# Crumar_D9U_Main.net
KiCad netlist of a schematic drawn in EAGLE
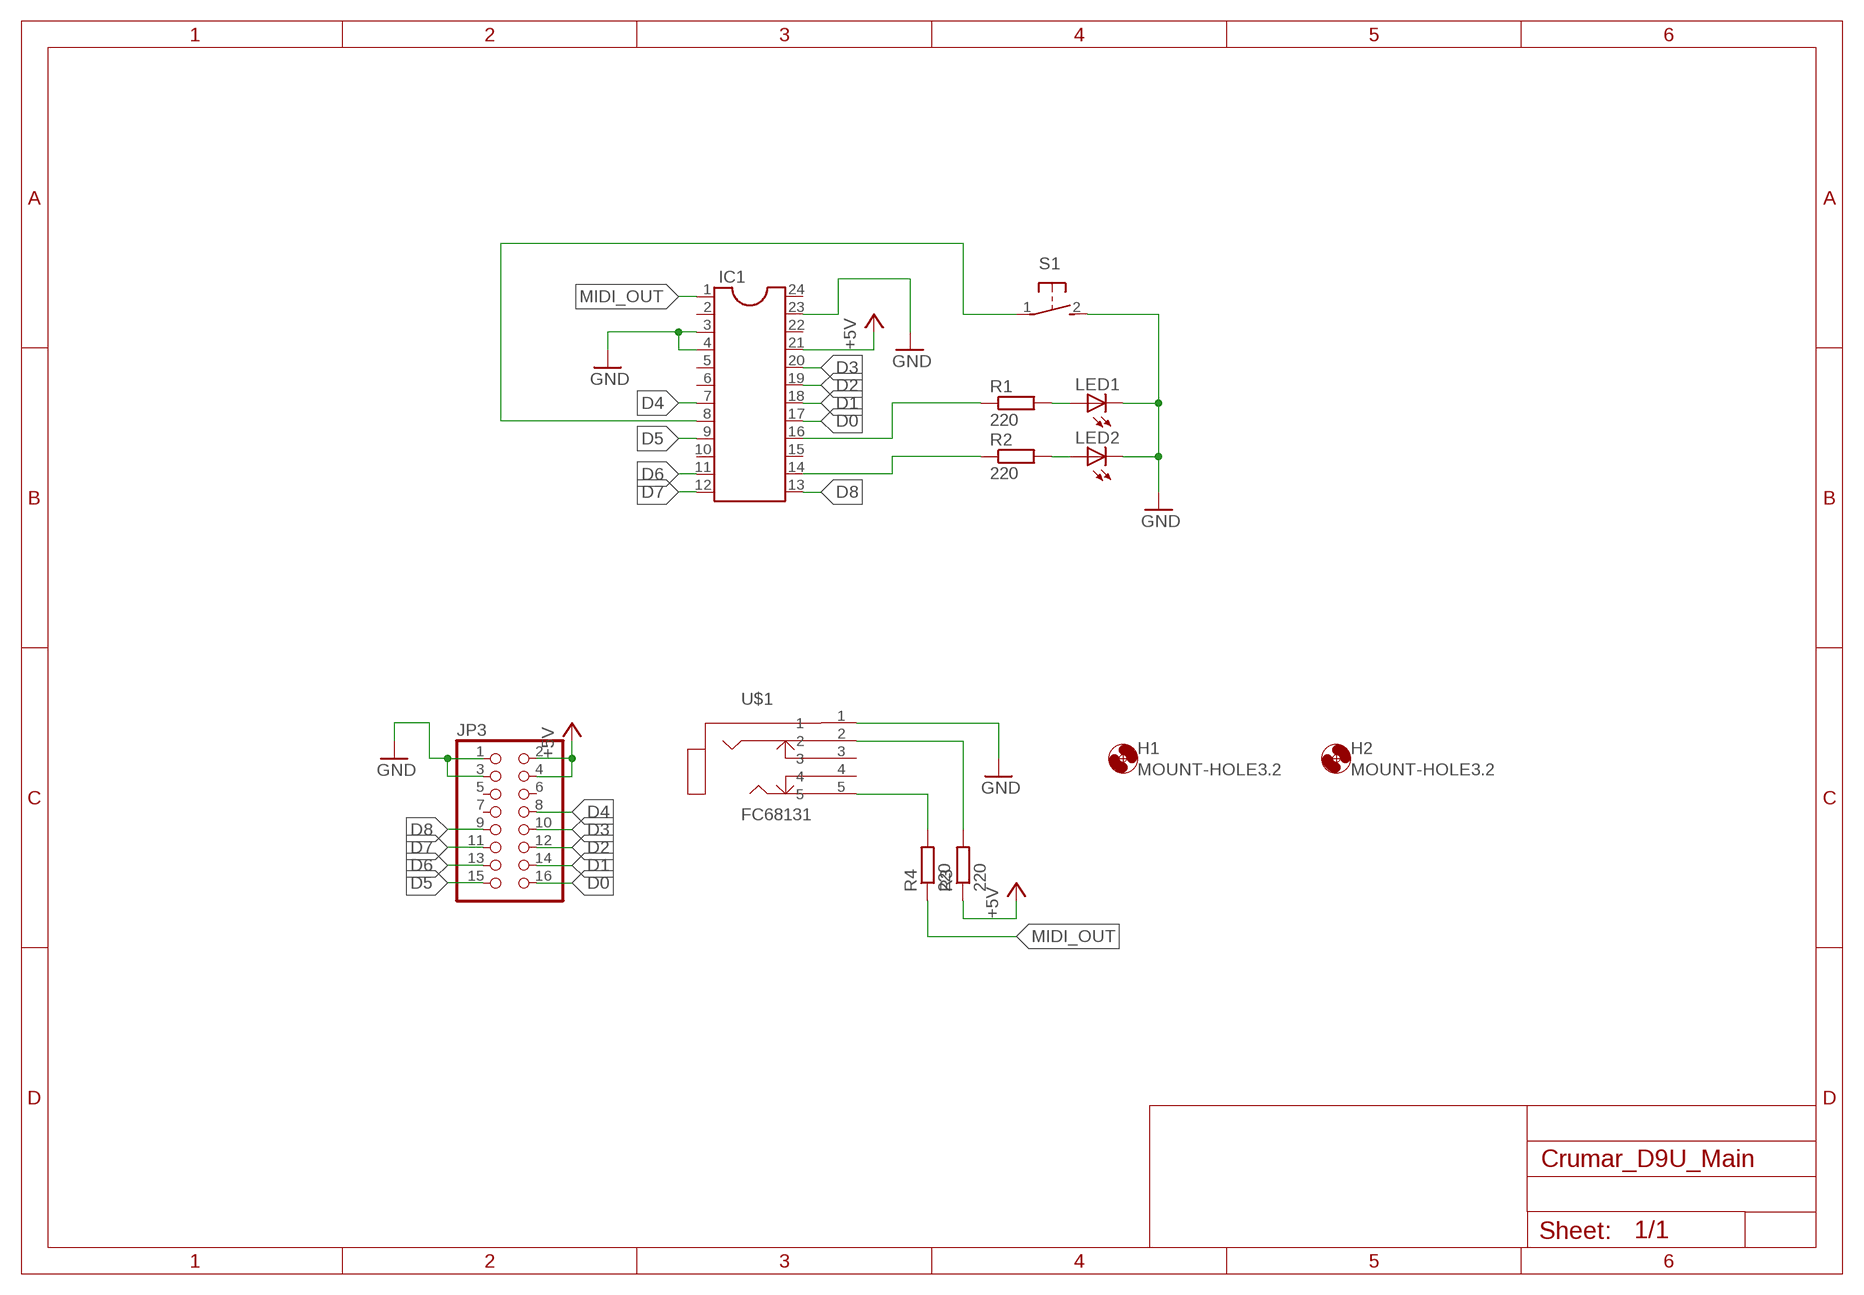
[diagram p0: schematic, sheet 1]

(export (version "E")
  (design (tool "Eeschema 10.0.6"))
  (components
    (comp (ref "H1")
      (value "MOUNT-HOLE3.2")
      (footprint "eagle-import:3,2")
      (libsource (lib "eagle-import") (part "MOUNT-HOLE3.2"))
    )
    (comp (ref "H2")
      (value "MOUNT-HOLE3.2")
      (footprint "eagle-import:3,2")
      (libsource (lib "eagle-import") (part "MOUNT-HOLE3.2"))
    )
    (comp (ref "IC1")
      (value "DIL24-6")
      (footprint "eagle-import:DIL24-6")
      (libsource (lib "eagle-import") (part "DIL24-6"))
    )
    (comp (ref "JP3")
      (value "PINHD-2X8")
      (footprint "eagle-import:2X08")
      (libsource (lib "eagle-import") (part "PINHD-2X8"))
    )
    (comp (ref "LED1")
      (value "LED3MM")
      (footprint "eagle-import:LED3MM")
      (libsource (lib "eagle-import") (part "LED3MM"))
    )
    (comp (ref "LED2")
      (value "LED3MM")
      (footprint "eagle-import:LED3MM")
      (libsource (lib "eagle-import") (part "LED3MM"))
    )
    (comp (ref "R1")
      (value "220")
      (footprint "eagle-import:0207_7")
      (libsource (lib "eagle-import") (part "R-EU_0207/7"))
    )
    (comp (ref "R2")
      (value "220")
      (footprint "eagle-import:0207_7")
      (libsource (lib "eagle-import") (part "R-EU_0207/7"))
    )
    (comp (ref "R3")
      (value "220")
      (footprint "eagle-import:0207_7")
      (libsource (lib "eagle-import") (part "R-EU_0207/7"))
    )
    (comp (ref "R4")
      (value "220")
      (footprint "eagle-import:0207_7")
      (libsource (lib "eagle-import") (part "R-EU_0207/7"))
    )
    (comp (ref "S1")
      (value "31-XX")
      (footprint "eagle-import:B3F-31XX")
      (fields (field (name "MPN") "B3F-3100"))
      (libsource (lib "eagle-import") (part "31-XX"))
    )
    (comp (ref "U$1")
      (value "FC68131")
      (footprint "eagle-import:FC68131-5P")
      (libsource (lib "eagle-import") (part "FC68131"))
    )
  )
  (nets
    (net (code "1") (name "+5V") (class "Default")
      (node (ref "IC1") (pin "21") (pinfunction "21_21") (pintype "passive"))
      (node (ref "JP3") (pin "2") (pinfunction "2_2") (pintype "passive"))
      (node (ref "JP3") (pin "4") (pinfunction "4_4") (pintype "passive"))
      (node (ref "R3") (pin "1") (pinfunction "1_1") (pintype "passive"))
    )
    (net (code "2") (name "D0") (class "Default")
      (node (ref "IC1") (pin "17") (pinfunction "17_17") (pintype "passive"))
      (node (ref "JP3") (pin "16") (pinfunction "16_16") (pintype "passive"))
    )
    (net (code "3") (name "D1") (class "Default")
      (node (ref "IC1") (pin "18") (pinfunction "18_18") (pintype "passive"))
      (node (ref "JP3") (pin "14") (pinfunction "14_14") (pintype "passive"))
    )
    (net (code "4") (name "D2") (class "Default")
      (node (ref "IC1") (pin "19") (pinfunction "19_19") (pintype "passive"))
      (node (ref "JP3") (pin "12") (pinfunction "12_12") (pintype "passive"))
    )
    (net (code "5") (name "D3") (class "Default")
      (node (ref "IC1") (pin "20") (pinfunction "20_20") (pintype "passive"))
      (node (ref "JP3") (pin "10") (pinfunction "10_10") (pintype "passive"))
    )
    (net (code "6") (name "D4") (class "Default")
      (node (ref "IC1") (pin "7") (pinfunction "7_7") (pintype "passive"))
      (node (ref "JP3") (pin "8") (pinfunction "8_8") (pintype "passive"))
    )
    (net (code "7") (name "D5") (class "Default")
      (node (ref "IC1") (pin "9") (pinfunction "9_9") (pintype "passive"))
      (node (ref "JP3") (pin "15") (pinfunction "15_15") (pintype "passive"))
    )
    (net (code "8") (name "D6") (class "Default")
      (node (ref "IC1") (pin "11") (pinfunction "11_11") (pintype "passive"))
      (node (ref "JP3") (pin "13") (pinfunction "13_13") (pintype "passive"))
    )
    (net (code "9") (name "D7") (class "Default")
      (node (ref "IC1") (pin "12") (pinfunction "12_12") (pintype "passive"))
      (node (ref "JP3") (pin "11") (pinfunction "11_11") (pintype "passive"))
    )
    (net (code "10") (name "D8") (class "Default")
      (node (ref "IC1") (pin "13") (pinfunction "13_13") (pintype "passive"))
      (node (ref "JP3") (pin "9") (pinfunction "9_9") (pintype "passive"))
    )
    (net (code "11") (name "GND") (class "Default")
      (node (ref "IC1") (pin "23") (pinfunction "23_23") (pintype "passive"))
      (node (ref "IC1") (pin "3") (pinfunction "3_3") (pintype "passive"))
      (node (ref "IC1") (pin "4") (pinfunction "4_4") (pintype "passive"))
      (node (ref "JP3") (pin "1") (pinfunction "1_1") (pintype "passive"))
      (node (ref "JP3") (pin "3") (pinfunction "3_3") (pintype "passive"))
      (node (ref "LED1") (pin "K") (pinfunction "C_K") (pintype "passive"))
      (node (ref "LED2") (pin "K") (pinfunction "C_K") (pintype "passive"))
      (node (ref "S1") (pin "2") (pinfunction "S_2") (pintype "passive"))
      (node (ref "U$1") (pin "1") (pinfunction "1_1") (pintype "bidirectional"))
    )
    (net (code "12") (name "MIDI_OUT") (class "Default")
      (node (ref "IC1") (pin "1") (pinfunction "1_1") (pintype "passive"))
      (node (ref "R4") (pin "1") (pinfunction "1_1") (pintype "passive"))
    )
    (net (code "13") (name "Net-(IC1-Pad14)") (class "Default")
      (node (ref "IC1") (pin "14") (pinfunction "14_14") (pintype "passive"))
      (node (ref "R2") (pin "1") (pinfunction "1_1") (pintype "passive"))
    )
    (net (code "14") (name "Net-(IC1-Pad16)") (class "Default")
      (node (ref "IC1") (pin "16") (pinfunction "16_16") (pintype "passive"))
      (node (ref "R1") (pin "1") (pinfunction "1_1") (pintype "passive"))
    )
    (net (code "15") (name "Net-(LED1-PadA)") (class "Default")
      (node (ref "LED1") (pin "A") (pinfunction "A_A") (pintype "passive"))
      (node (ref "R1") (pin "2") (pinfunction "2_2") (pintype "passive"))
    )
    (net (code "16") (name "Net-(LED2-PadA)") (class "Default")
      (node (ref "LED2") (pin "A") (pinfunction "A_A") (pintype "passive"))
      (node (ref "R2") (pin "2") (pinfunction "2_2") (pintype "passive"))
    )
    (net (code "17") (name "Net-(R3-Pad2)") (class "Default")
      (node (ref "R3") (pin "2") (pinfunction "2_2") (pintype "passive"))
      (node (ref "U$1") (pin "2") (pinfunction "2_2") (pintype "bidirectional"))
    )
    (net (code "18") (name "Net-(R4-Pad2)") (class "Default")
      (node (ref "R4") (pin "2") (pinfunction "2_2") (pintype "passive"))
      (node (ref "U$1") (pin "5") (pinfunction "5_5") (pintype "bidirectional"))
    )
    (net (code "19") (name "Net-(S1-P)") (class "Default")
      (node (ref "IC1") (pin "8") (pinfunction "8_8") (pintype "passive"))
      (node (ref "S1") (pin "1") (pinfunction "P_1") (pintype "passive"))
    )
    (net (code "20") (name "unconnected-(IC1-Pad2)") (class "Default")
      (node (ref "IC1") (pin "2") (pinfunction "2_2") (pintype "passive"))
    )
    (net (code "21") (name "unconnected-(IC1-Pad5)") (class "Default")
      (node (ref "IC1") (pin "5") (pinfunction "5_5") (pintype "passive"))
    )
    (net (code "22") (name "unconnected-(IC1-Pad6)") (class "Default")
      (node (ref "IC1") (pin "6") (pinfunction "6_6") (pintype "passive"))
    )
    (net (code "23") (name "unconnected-(IC1-Pad10)") (class "Default")
      (node (ref "IC1") (pin "10") (pinfunction "10_10") (pintype "passive"))
    )
    (net (code "24") (name "unconnected-(IC1-Pad15)") (class "Default")
      (node (ref "IC1") (pin "15") (pinfunction "15_15") (pintype "passive"))
    )
    (net (code "25") (name "unconnected-(IC1-Pad22)") (class "Default")
      (node (ref "IC1") (pin "22") (pinfunction "22_22") (pintype "passive"))
    )
    (net (code "26") (name "unconnected-(IC1-Pad24)") (class "Default")
      (node (ref "IC1") (pin "24") (pinfunction "24_24") (pintype "passive"))
    )
    (net (code "27") (name "unconnected-(JP3-Pad5)") (class "Default")
      (node (ref "JP3") (pin "5") (pinfunction "5_5") (pintype "passive"))
    )
    (net (code "28") (name "unconnected-(JP3-Pad6)") (class "Default")
      (node (ref "JP3") (pin "6") (pinfunction "6_6") (pintype "passive"))
    )
    (net (code "29") (name "unconnected-(JP3-Pad7)") (class "Default")
      (node (ref "JP3") (pin "7") (pinfunction "7_7") (pintype "passive"))
    )
    (net (code "30") (name "unconnected-(U$1-Pad3)") (class "Default")
      (node (ref "U$1") (pin "3") (pinfunction "3_3") (pintype "bidirectional"))
    )
    (net (code "31") (name "unconnected-(U$1-Pad4)") (class "Default")
      (node (ref "U$1") (pin "4") (pinfunction "4_4") (pintype "bidirectional"))
    )
  )
)
